# eeZeePower.net
KiCad netlist of a schematic drawn in EAGLE
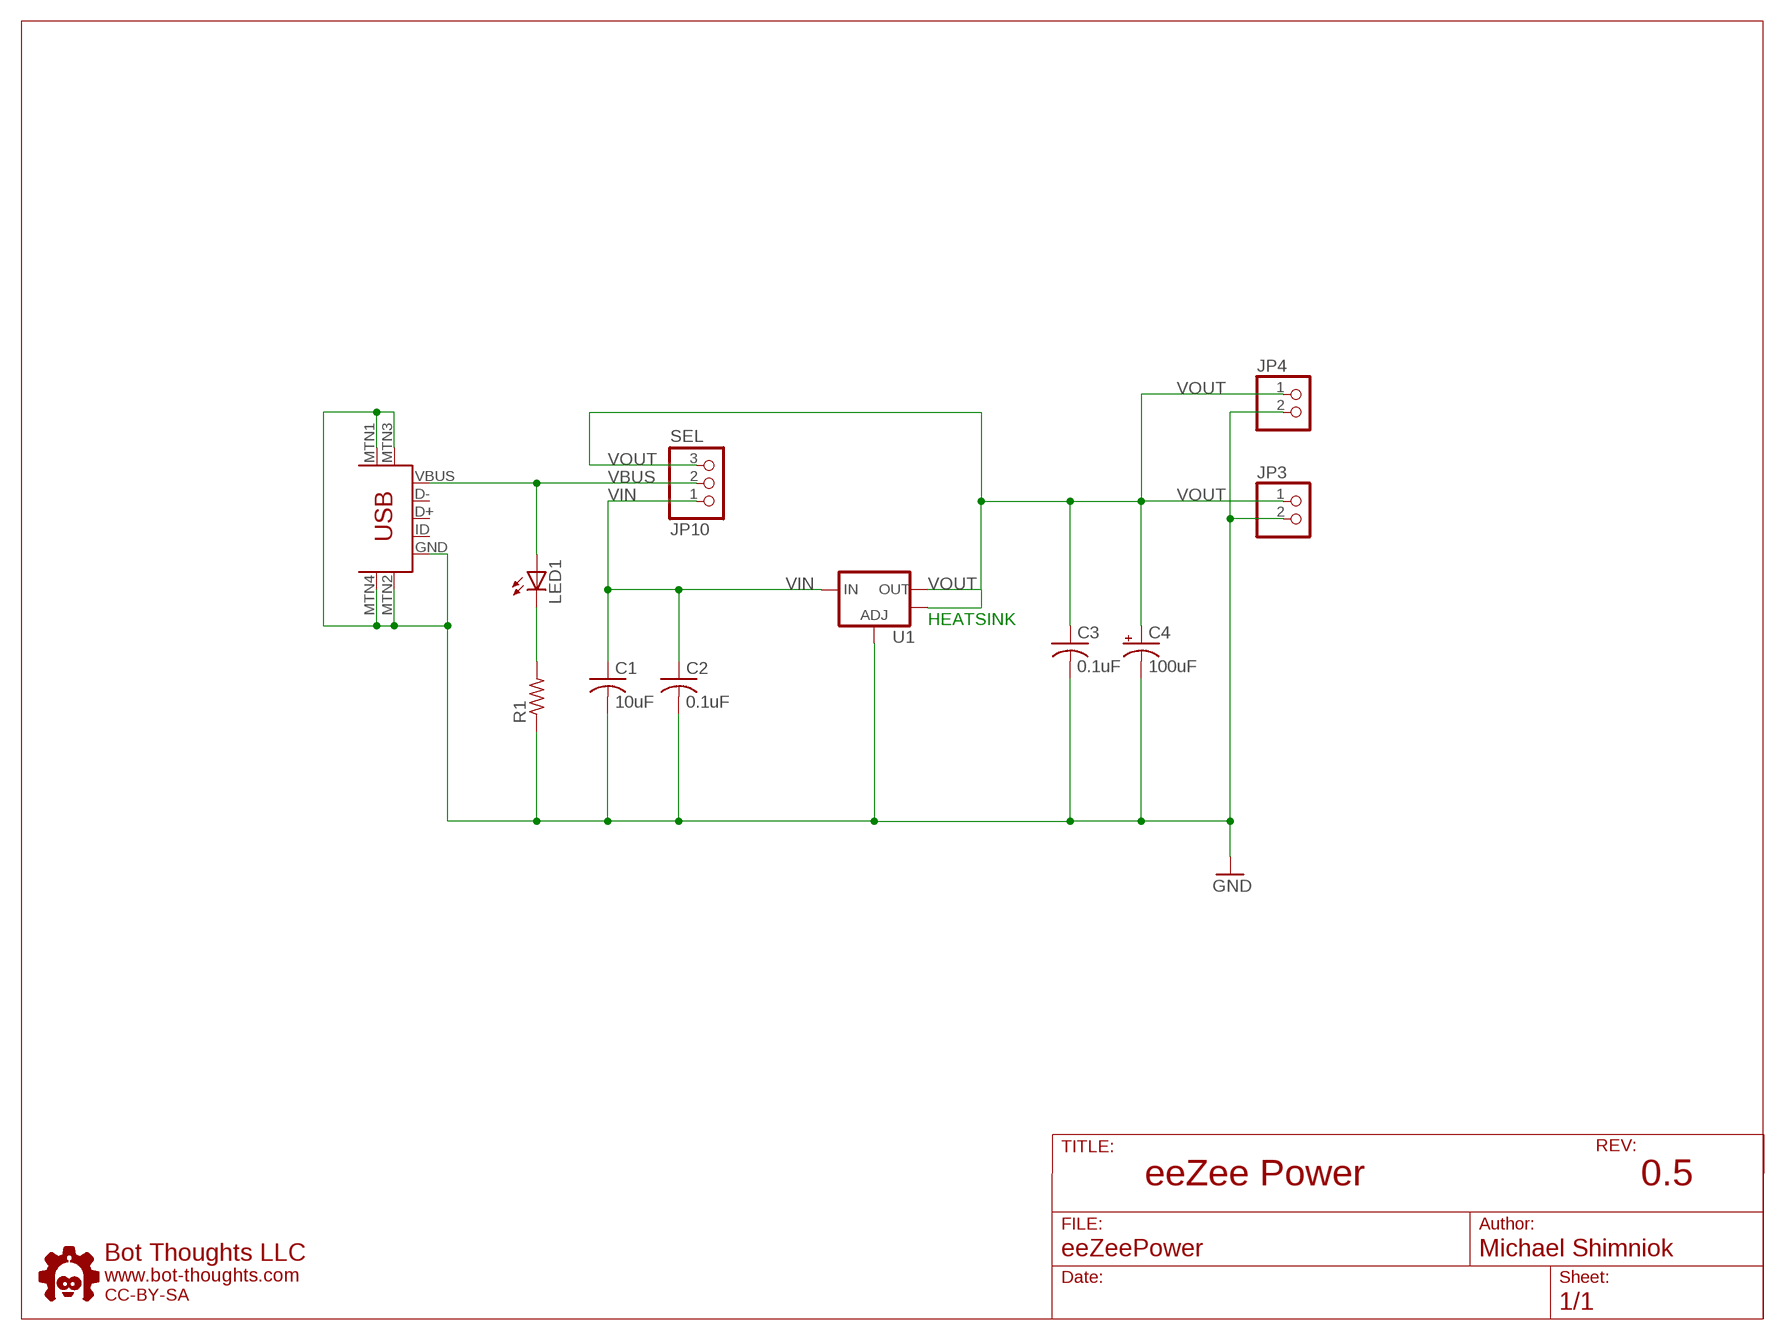
[diagram p0: schematic, sheet 1]

(export (version "E")
  (design (tool "Eeschema 10.0.6"))
  (components
    (comp (ref "C1")
      (value "10uF")
      (footprint "eagle-import:C1206")
      (libsource (lib "eagle-import") (part "C-USC1206"))
    )
    (comp (ref "C2")
      (value "0.1uF")
      (footprint "eagle-import:C0603")
      (libsource (lib "eagle-import") (part "C-USC0603"))
    )
    (comp (ref "C3")
      (value "0.1uF")
      (footprint "eagle-import:C0603")
      (libsource (lib "eagle-import") (part "C-USC0603"))
    )
    (comp (ref "C4")
      (value "100uF")
      (footprint "eagle-import:SMC_B")
      (libsource (lib "eagle-import") (part "CPOL-USSMCB"))
    )
    (comp (ref "JP3")
      (value "PINHD-1X02_2.54-S")
      (footprint "eagle-import:1X02-S")
      (libsource (lib "eagle-import") (part "PINHD-1X02_2.54-S"))
    )
    (comp (ref "JP4")
      (value "PINHD-1X02_2.54-S")
      (footprint "eagle-import:1X02-S")
      (libsource (lib "eagle-import") (part "PINHD-1X02_2.54-S"))
    )
    (comp (ref "JP10")
      (value "SEL")
      (footprint "eagle-import:1X03-S")
      (libsource (lib "eagle-import") (part "PINHD-1X03_2.54-S"))
    )
    (comp (ref "LED1")
      (value "LEDCHIPLED_1206")
      (footprint "eagle-import:CHIPLED_1206")
      (libsource (lib "eagle-import") (part "LEDCHIPLED_1206"))
    )
    (comp (ref "R1")
      (value "R-US_R0603")
      (footprint "eagle-import:R0603")
      (libsource (lib "eagle-import") (part "R-US_R0603"))
    )
    (comp (ref "U$1")
      (value "USB-MINIB-5PIN")
      (footprint "eagle-import:USB-MINIB")
      (libsource (lib "eagle-import") (part "USB-MINIB-5PIN"))
    )
    (comp (ref "U$2")
      (value "BTLOGO-LOGO-MD")
      (footprint "eagle-import:BTLOGOM")
      (libsource (lib "eagle-import") (part "BTLOGO-LOGO-MD"))
    )
    (comp (ref "U1")
      (value "V_REG_LM1117SOT223")
      (footprint "eagle-import:SOT223")
      (libsource (lib "eagle-import") (part "V_REG_LM1117SOT223"))
    )
  )
  (nets
    (net (code "1") (name "/VBUS") (class "Default")
      (node (ref "JP10") (pin "2") (pinfunction "2_2") (pintype "passive"))
      (node (ref "LED1") (pin "A") (pinfunction "A_A") (pintype "passive"))
      (node (ref "U$1") (pin "VBUS") (pinfunction "VBUS_VBUS") (pintype "bidirectional"))
    )
    (net (code "2") (name "/VIN") (class "Default")
      (node (ref "C1") (pin "1") (pinfunction "1_1") (pintype "passive"))
      (node (ref "C2") (pin "1") (pinfunction "1_1") (pintype "passive"))
      (node (ref "JP10") (pin "1") (pinfunction "1_1") (pintype "passive"))
      (node (ref "U1") (pin "3") (pinfunction "IN_3") (pintype "input"))
    )
    (net (code "3") (name "/VOUT") (class "Default")
      (node (ref "C3") (pin "1") (pinfunction "1_1") (pintype "passive"))
      (node (ref "C4") (pin "+") (pinfunction "+_+") (pintype "passive"))
      (node (ref "JP10") (pin "3") (pinfunction "3_3") (pintype "passive"))
      (node (ref "JP3") (pin "1") (pinfunction "1_1") (pintype "passive"))
      (node (ref "JP4") (pin "1") (pinfunction "1_1") (pintype "passive"))
      (node (ref "U1") (pin "2") (pinfunction "OUT_2") (pintype "output"))
      (node (ref "U1") (pin "4") (pinfunction "OUT_4") (pintype "output"))
    )
    (net (code "4") (name "GND") (class "Default")
      (node (ref "C1") (pin "2") (pinfunction "2_2") (pintype "passive"))
      (node (ref "C2") (pin "2") (pinfunction "2_2") (pintype "passive"))
      (node (ref "C3") (pin "2") (pinfunction "2_2") (pintype "passive"))
      (node (ref "C4") (pin "-") (pinfunction "-_-") (pintype "passive"))
      (node (ref "JP3") (pin "2") (pinfunction "2_2") (pintype "passive"))
      (node (ref "JP4") (pin "2") (pinfunction "2_2") (pintype "passive"))
      (node (ref "R1") (pin "1") (pinfunction "1_1") (pintype "passive"))
      (node (ref "U$1") (pin "GND") (pinfunction "GND_GND") (pintype "bidirectional"))
      (node (ref "U$1") (pin "MTN1") (pinfunction "MTN2_MTN1") (pintype "bidirectional"))
      (node (ref "U$1") (pin "MTN2") (pinfunction "MTN3_MTN2") (pintype "bidirectional"))
      (node (ref "U$1") (pin "MTN3") (pinfunction "MTN1_MTN3") (pintype "bidirectional"))
      (node (ref "U$1") (pin "MTN4") (pinfunction "MTN4_MTN4") (pintype "bidirectional"))
      (node (ref "U1") (pin "1") (pinfunction "ADJ_1") (pintype "input"))
    )
    (net (code "5") (name "Net-(LED1-PadC)") (class "Default")
      (node (ref "LED1") (pin "C") (pinfunction "C_C") (pintype "passive"))
      (node (ref "R1") (pin "2") (pinfunction "2_2") (pintype "passive"))
    )
    (net (code "6") (name "unconnected-(U$1-PadD+)") (class "Default")
      (node (ref "U$1") (pin "D+") (pinfunction "D+_D+") (pintype "bidirectional"))
    )
    (net (code "7") (name "unconnected-(U$1-PadD-)") (class "Default")
      (node (ref "U$1") (pin "D-") (pinfunction "D-_D-") (pintype "bidirectional"))
    )
    (net (code "8") (name "unconnected-(U$1-PadID)") (class "Default")
      (node (ref "U$1") (pin "ID") (pinfunction "ID_ID") (pintype "bidirectional"))
    )
  )
)
